# ECE3992_APS.net
KiCad netlist of a schematic drawn in EAGLE
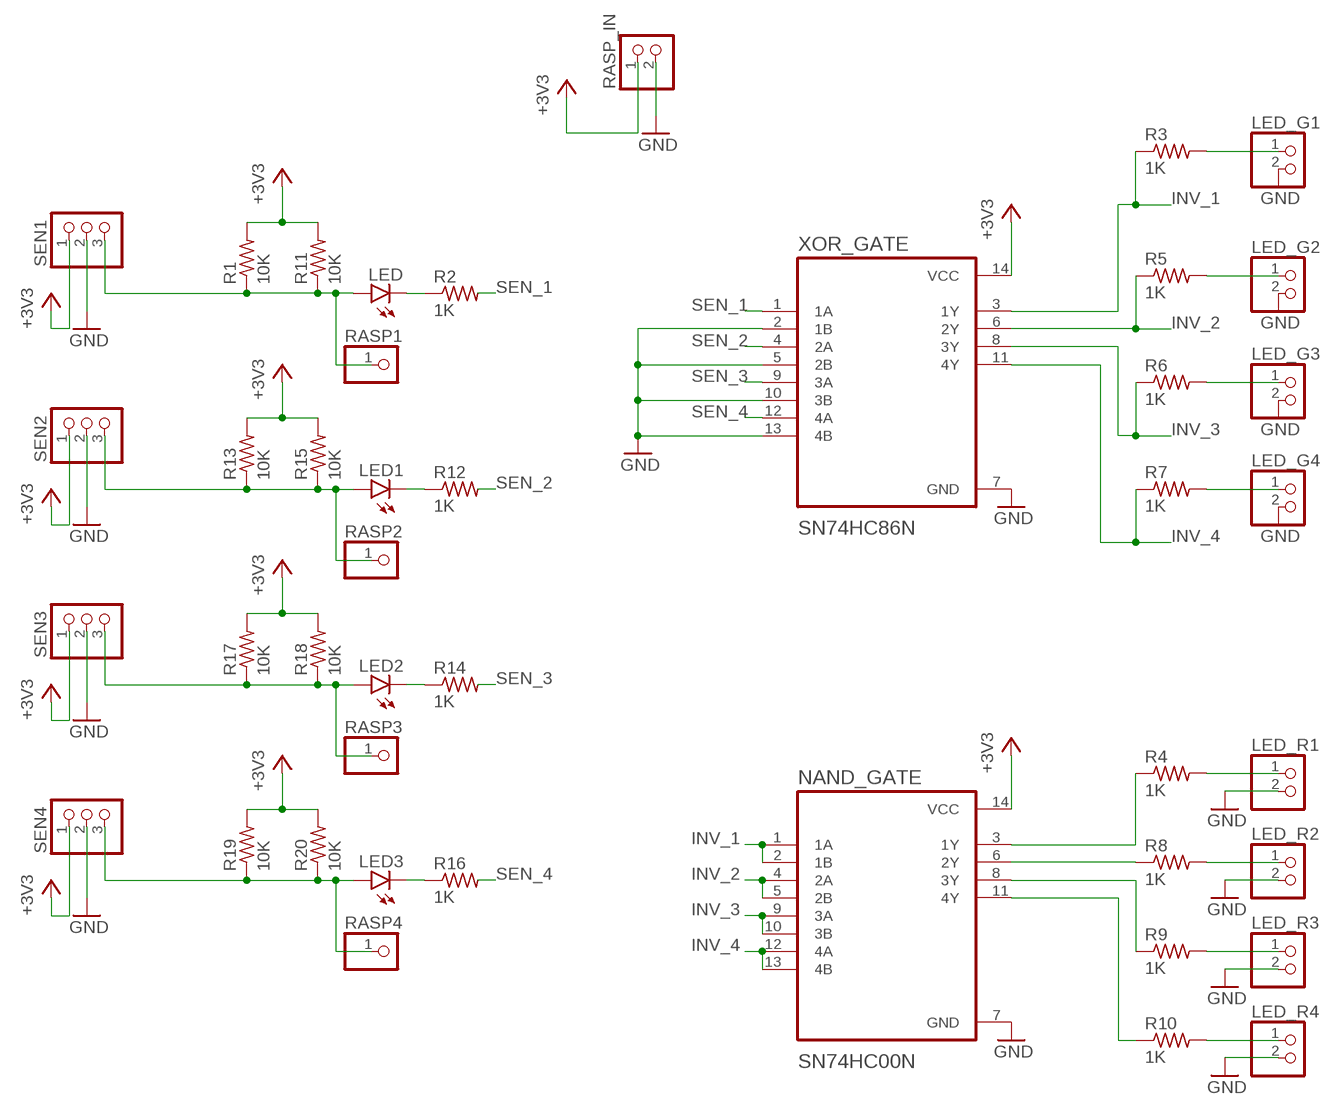
[diagram p0: schematic, sheet 1]

(export (version "E")
  (design (tool "Eeschema 10.0.6"))
  (components
    (comp (ref "LED")
      (value "LED5MM")
      (footprint "eagle-import:LED5MM")
      (libsource (lib "eagle-import") (part "LED5MM"))
    )
    (comp (ref "LED1")
      (value "LED5MM")
      (footprint "eagle-import:LED5MM")
      (libsource (lib "eagle-import") (part "LED5MM"))
    )
    (comp (ref "LED2")
      (value "LED5MM")
      (footprint "eagle-import:LED5MM")
      (libsource (lib "eagle-import") (part "LED5MM"))
    )
    (comp (ref "LED3")
      (value "LED5MM")
      (footprint "eagle-import:LED5MM")
      (libsource (lib "eagle-import") (part "LED5MM"))
    )
    (comp (ref "LED_G1")
      (value "PINHD-1X2")
      (footprint "eagle-import:1X02")
      (libsource (lib "eagle-import") (part "PINHD-1X2"))
    )
    (comp (ref "LED_G2")
      (value "PINHD-1X2")
      (footprint "eagle-import:1X02")
      (libsource (lib "eagle-import") (part "PINHD-1X2"))
    )
    (comp (ref "LED_G3")
      (value "PINHD-1X2")
      (footprint "eagle-import:1X02")
      (libsource (lib "eagle-import") (part "PINHD-1X2"))
    )
    (comp (ref "LED_G4")
      (value "PINHD-1X2")
      (footprint "eagle-import:1X02")
      (libsource (lib "eagle-import") (part "PINHD-1X2"))
    )
    (comp (ref "LED_R1")
      (value "PINHD-1X2")
      (footprint "eagle-import:1X02")
      (libsource (lib "eagle-import") (part "PINHD-1X2"))
    )
    (comp (ref "LED_R2")
      (value "PINHD-1X2")
      (footprint "eagle-import:1X02")
      (libsource (lib "eagle-import") (part "PINHD-1X2"))
    )
    (comp (ref "LED_R3")
      (value "PINHD-1X2")
      (footprint "eagle-import:1X02")
      (libsource (lib "eagle-import") (part "PINHD-1X2"))
    )
    (comp (ref "LED_R4")
      (value "PINHD-1X2")
      (footprint "eagle-import:1X02")
      (libsource (lib "eagle-import") (part "PINHD-1X2"))
    )
    (comp (ref "NAND_GATE")
      (value "SN74HC00N")
      (footprint "eagle-import:DIP794W45P254L1969H508Q14")
      (fields (field (name "MF") "Texas Instruments"))
      (libsource (lib "eagle-import") (part "SN74HC00N"))
    )
    (comp (ref "R1")
      (value "10K")
      (footprint "eagle-import:0207_10")
      (libsource (lib "eagle-import") (part "R-US_0207/10"))
    )
    (comp (ref "R2")
      (value "1K")
      (footprint "eagle-import:0207_10")
      (libsource (lib "eagle-import") (part "R-US_0207/10"))
    )
    (comp (ref "R3")
      (value "1K")
      (footprint "eagle-import:0207_10")
      (libsource (lib "eagle-import") (part "R-US_0207/10"))
    )
    (comp (ref "R4")
      (value "1K")
      (footprint "eagle-import:0207_10")
      (libsource (lib "eagle-import") (part "R-US_0207/10"))
    )
    (comp (ref "R5")
      (value "1K")
      (footprint "eagle-import:0207_10")
      (libsource (lib "eagle-import") (part "R-US_0207/10"))
    )
    (comp (ref "R6")
      (value "1K")
      (footprint "eagle-import:0207_10")
      (libsource (lib "eagle-import") (part "R-US_0207/10"))
    )
    (comp (ref "R7")
      (value "1K")
      (footprint "eagle-import:0207_10")
      (libsource (lib "eagle-import") (part "R-US_0207/10"))
    )
    (comp (ref "R8")
      (value "1K")
      (footprint "eagle-import:0207_10")
      (libsource (lib "eagle-import") (part "R-US_0207/10"))
    )
    (comp (ref "R9")
      (value "1K")
      (footprint "eagle-import:0207_10")
      (libsource (lib "eagle-import") (part "R-US_0207/10"))
    )
    (comp (ref "R10")
      (value "1K")
      (footprint "eagle-import:0207_10")
      (libsource (lib "eagle-import") (part "R-US_0207/10"))
    )
    (comp (ref "R11")
      (value "10K")
      (footprint "eagle-import:0207_10")
      (libsource (lib "eagle-import") (part "R-US_0207/10"))
    )
    (comp (ref "R12")
      (value "1K")
      (footprint "eagle-import:0207_10")
      (libsource (lib "eagle-import") (part "R-US_0207/10"))
    )
    (comp (ref "R13")
      (value "10K")
      (footprint "eagle-import:0207_10")
      (libsource (lib "eagle-import") (part "R-US_0207/10"))
    )
    (comp (ref "R14")
      (value "1K")
      (footprint "eagle-import:0207_10")
      (libsource (lib "eagle-import") (part "R-US_0207/10"))
    )
    (comp (ref "R15")
      (value "10K")
      (footprint "eagle-import:0207_10")
      (libsource (lib "eagle-import") (part "R-US_0207/10"))
    )
    (comp (ref "R16")
      (value "1K")
      (footprint "eagle-import:0207_10")
      (libsource (lib "eagle-import") (part "R-US_0207/10"))
    )
    (comp (ref "R17")
      (value "10K")
      (footprint "eagle-import:0207_10")
      (libsource (lib "eagle-import") (part "R-US_0207/10"))
    )
    (comp (ref "R18")
      (value "10K")
      (footprint "eagle-import:0207_10")
      (libsource (lib "eagle-import") (part "R-US_0207/10"))
    )
    (comp (ref "R19")
      (value "10K")
      (footprint "eagle-import:0207_10")
      (libsource (lib "eagle-import") (part "R-US_0207/10"))
    )
    (comp (ref "R20")
      (value "10K")
      (footprint "eagle-import:0207_10")
      (libsource (lib "eagle-import") (part "R-US_0207/10"))
    )
    (comp (ref "RASP1")
      (value "PINHD-1X1")
      (footprint "eagle-import:1X01")
      (libsource (lib "eagle-import") (part "PINHD-1X1"))
    )
    (comp (ref "RASP2")
      (value "PINHD-1X1")
      (footprint "eagle-import:1X01")
      (libsource (lib "eagle-import") (part "PINHD-1X1"))
    )
    (comp (ref "RASP3")
      (value "PINHD-1X1")
      (footprint "eagle-import:1X01")
      (libsource (lib "eagle-import") (part "PINHD-1X1"))
    )
    (comp (ref "RASP4")
      (value "PINHD-1X1")
      (footprint "eagle-import:1X01")
      (libsource (lib "eagle-import") (part "PINHD-1X1"))
    )
    (comp (ref "RASP_IN")
      (value "PINHD-1X2")
      (footprint "eagle-import:1X02")
      (libsource (lib "eagle-import") (part "PINHD-1X2"))
    )
    (comp (ref "SEN1")
      (value "PINHD-1X3")
      (footprint "eagle-import:1X03")
      (libsource (lib "eagle-import") (part "PINHD-1X3"))
    )
    (comp (ref "SEN2")
      (value "PINHD-1X3")
      (footprint "eagle-import:1X03")
      (libsource (lib "eagle-import") (part "PINHD-1X3"))
    )
    (comp (ref "SEN3")
      (value "PINHD-1X3")
      (footprint "eagle-import:1X03")
      (libsource (lib "eagle-import") (part "PINHD-1X3"))
    )
    (comp (ref "SEN4")
      (value "PINHD-1X3")
      (footprint "eagle-import:1X03")
      (libsource (lib "eagle-import") (part "PINHD-1X3"))
    )
    (comp (ref "XOR_GATE")
      (value "SN74HC86N")
      (footprint "eagle-import:DIP794W45P254L1969H508Q14")
      (fields (field (name "MF") "Texas Instruments"))
      (libsource (lib "eagle-import") (part "SN74HC86N"))
    )
  )
  (nets
    (net (code "1") (name "+3V3") (class "Default")
      (node (ref "NAND_GATE") (pin "14") (pinfunction "VCC_14") (pintype "power_in"))
      (node (ref "R1") (pin "2") (pinfunction "2_2") (pintype "passive"))
      (node (ref "R11") (pin "2") (pinfunction "2_2") (pintype "passive"))
      (node (ref "R13") (pin "2") (pinfunction "2_2") (pintype "passive"))
      (node (ref "R15") (pin "2") (pinfunction "2_2") (pintype "passive"))
      (node (ref "R17") (pin "2") (pinfunction "2_2") (pintype "passive"))
      (node (ref "R18") (pin "2") (pinfunction "2_2") (pintype "passive"))
      (node (ref "R19") (pin "2") (pinfunction "2_2") (pintype "passive"))
      (node (ref "R20") (pin "2") (pinfunction "2_2") (pintype "passive"))
      (node (ref "RASP_IN") (pin "1") (pinfunction "1_1") (pintype "passive"))
      (node (ref "SEN1") (pin "1") (pinfunction "1_1") (pintype "passive"))
      (node (ref "SEN2") (pin "1") (pinfunction "1_1") (pintype "passive"))
      (node (ref "SEN3") (pin "1") (pinfunction "1_1") (pintype "passive"))
      (node (ref "SEN4") (pin "1") (pinfunction "1_1") (pintype "passive"))
      (node (ref "XOR_GATE") (pin "14") (pinfunction "VCC_14") (pintype "power_in"))
    )
    (net (code "2") (name "/INV_1") (class "Default")
      (node (ref "NAND_GATE") (pin "1") (pinfunction "1A_1") (pintype "input"))
      (node (ref "NAND_GATE") (pin "2") (pinfunction "1B_2") (pintype "input"))
      (node (ref "R3") (pin "1") (pinfunction "1_1") (pintype "passive"))
      (node (ref "XOR_GATE") (pin "3") (pinfunction "1Y_3") (pintype "output"))
    )
    (net (code "3") (name "/INV_2") (class "Default")
      (node (ref "NAND_GATE") (pin "4") (pinfunction "2A_4") (pintype "input"))
      (node (ref "NAND_GATE") (pin "5") (pinfunction "2B_5") (pintype "input"))
      (node (ref "R5") (pin "1") (pinfunction "1_1") (pintype "passive"))
      (node (ref "XOR_GATE") (pin "6") (pinfunction "2Y_6") (pintype "output"))
    )
    (net (code "4") (name "/INV_3") (class "Default")
      (node (ref "NAND_GATE") (pin "10") (pinfunction "3B_10") (pintype "input"))
      (node (ref "NAND_GATE") (pin "9") (pinfunction "3A_9") (pintype "input"))
      (node (ref "R6") (pin "1") (pinfunction "1_1") (pintype "passive"))
      (node (ref "XOR_GATE") (pin "8") (pinfunction "3Y_8") (pintype "output"))
    )
    (net (code "5") (name "/INV_4") (class "Default")
      (node (ref "NAND_GATE") (pin "12") (pinfunction "4A_12") (pintype "input"))
      (node (ref "NAND_GATE") (pin "13") (pinfunction "4B_13") (pintype "input"))
      (node (ref "R7") (pin "1") (pinfunction "1_1") (pintype "passive"))
      (node (ref "XOR_GATE") (pin "11") (pinfunction "4Y_11") (pintype "output"))
    )
    (net (code "6") (name "/SEN_1") (class "Default")
      (node (ref "R2") (pin "2") (pinfunction "2_2") (pintype "passive"))
      (node (ref "XOR_GATE") (pin "1") (pinfunction "1A_1") (pintype "input"))
    )
    (net (code "7") (name "/SEN_2") (class "Default")
      (node (ref "R12") (pin "2") (pinfunction "2_2") (pintype "passive"))
      (node (ref "XOR_GATE") (pin "4") (pinfunction "2A_4") (pintype "input"))
    )
    (net (code "8") (name "/SEN_3") (class "Default")
      (node (ref "R14") (pin "2") (pinfunction "2_2") (pintype "passive"))
      (node (ref "XOR_GATE") (pin "9") (pinfunction "3A_9") (pintype "input"))
    )
    (net (code "9") (name "/SEN_4") (class "Default")
      (node (ref "R16") (pin "2") (pinfunction "2_2") (pintype "passive"))
      (node (ref "XOR_GATE") (pin "12") (pinfunction "4A_12") (pintype "input"))
    )
    (net (code "10") (name "GND") (class "Default")
      (node (ref "LED_G1") (pin "2") (pinfunction "2_2") (pintype "passive"))
      (node (ref "LED_G2") (pin "2") (pinfunction "2_2") (pintype "passive"))
      (node (ref "LED_G3") (pin "2") (pinfunction "2_2") (pintype "passive"))
      (node (ref "LED_G4") (pin "2") (pinfunction "2_2") (pintype "passive"))
      (node (ref "LED_R1") (pin "2") (pinfunction "2_2") (pintype "passive"))
      (node (ref "LED_R2") (pin "2") (pinfunction "2_2") (pintype "passive"))
      (node (ref "LED_R3") (pin "2") (pinfunction "2_2") (pintype "passive"))
      (node (ref "LED_R4") (pin "2") (pinfunction "2_2") (pintype "passive"))
      (node (ref "NAND_GATE") (pin "7") (pinfunction "GND_7") (pintype "power_in"))
      (node (ref "RASP_IN") (pin "2") (pinfunction "2_2") (pintype "passive"))
      (node (ref "SEN1") (pin "2") (pinfunction "2_2") (pintype "passive"))
      (node (ref "SEN2") (pin "2") (pinfunction "2_2") (pintype "passive"))
      (node (ref "SEN3") (pin "2") (pinfunction "2_2") (pintype "passive"))
      (node (ref "SEN4") (pin "2") (pinfunction "2_2") (pintype "passive"))
      (node (ref "XOR_GATE") (pin "10") (pinfunction "3B_10") (pintype "input"))
      (node (ref "XOR_GATE") (pin "13") (pinfunction "4B_13") (pintype "input"))
      (node (ref "XOR_GATE") (pin "2") (pinfunction "1B_2") (pintype "input"))
      (node (ref "XOR_GATE") (pin "5") (pinfunction "2B_5") (pintype "input"))
      (node (ref "XOR_GATE") (pin "7") (pinfunction "GND_7") (pintype "power_in"))
    )
    (net (code "11") (name "Net-(LED-C)") (class "Default")
      (node (ref "LED") (pin "K") (pinfunction "C_K") (pintype "passive"))
      (node (ref "R2") (pin "1") (pinfunction "1_1") (pintype "passive"))
    )
    (net (code "12") (name "Net-(LED-PadA)") (class "Default")
      (node (ref "LED") (pin "A") (pinfunction "A_A") (pintype "passive"))
      (node (ref "R1") (pin "1") (pinfunction "1_1") (pintype "passive"))
      (node (ref "R11") (pin "1") (pinfunction "1_1") (pintype "passive"))
      (node (ref "RASP1") (pin "1") (pinfunction "1_1") (pintype "passive"))
      (node (ref "SEN1") (pin "3") (pinfunction "3_3") (pintype "passive"))
    )
    (net (code "13") (name "Net-(LED1-C)") (class "Default")
      (node (ref "LED1") (pin "K") (pinfunction "C_K") (pintype "passive"))
      (node (ref "R12") (pin "1") (pinfunction "1_1") (pintype "passive"))
    )
    (net (code "14") (name "Net-(LED1-PadA)") (class "Default")
      (node (ref "LED1") (pin "A") (pinfunction "A_A") (pintype "passive"))
      (node (ref "R13") (pin "1") (pinfunction "1_1") (pintype "passive"))
      (node (ref "R15") (pin "1") (pinfunction "1_1") (pintype "passive"))
      (node (ref "RASP2") (pin "1") (pinfunction "1_1") (pintype "passive"))
      (node (ref "SEN2") (pin "3") (pinfunction "3_3") (pintype "passive"))
    )
    (net (code "15") (name "Net-(LED2-C)") (class "Default")
      (node (ref "LED2") (pin "K") (pinfunction "C_K") (pintype "passive"))
      (node (ref "R14") (pin "1") (pinfunction "1_1") (pintype "passive"))
    )
    (net (code "16") (name "Net-(LED2-PadA)") (class "Default")
      (node (ref "LED2") (pin "A") (pinfunction "A_A") (pintype "passive"))
      (node (ref "R17") (pin "1") (pinfunction "1_1") (pintype "passive"))
      (node (ref "R18") (pin "1") (pinfunction "1_1") (pintype "passive"))
      (node (ref "RASP3") (pin "1") (pinfunction "1_1") (pintype "passive"))
      (node (ref "SEN3") (pin "3") (pinfunction "3_3") (pintype "passive"))
    )
    (net (code "17") (name "Net-(LED3-C)") (class "Default")
      (node (ref "LED3") (pin "K") (pinfunction "C_K") (pintype "passive"))
      (node (ref "R16") (pin "1") (pinfunction "1_1") (pintype "passive"))
    )
    (net (code "18") (name "Net-(LED3-PadA)") (class "Default")
      (node (ref "LED3") (pin "A") (pinfunction "A_A") (pintype "passive"))
      (node (ref "R19") (pin "1") (pinfunction "1_1") (pintype "passive"))
      (node (ref "R20") (pin "1") (pinfunction "1_1") (pintype "passive"))
      (node (ref "RASP4") (pin "1") (pinfunction "1_1") (pintype "passive"))
      (node (ref "SEN4") (pin "3") (pinfunction "3_3") (pintype "passive"))
    )
    (net (code "19") (name "Net-(LED_G1-Pad1)") (class "Default")
      (node (ref "LED_G1") (pin "1") (pinfunction "1_1") (pintype "passive"))
      (node (ref "R3") (pin "2") (pinfunction "2_2") (pintype "passive"))
    )
    (net (code "20") (name "Net-(LED_G2-Pad1)") (class "Default")
      (node (ref "LED_G2") (pin "1") (pinfunction "1_1") (pintype "passive"))
      (node (ref "R5") (pin "2") (pinfunction "2_2") (pintype "passive"))
    )
    (net (code "21") (name "Net-(LED_G3-Pad1)") (class "Default")
      (node (ref "LED_G3") (pin "1") (pinfunction "1_1") (pintype "passive"))
      (node (ref "R6") (pin "2") (pinfunction "2_2") (pintype "passive"))
    )
    (net (code "22") (name "Net-(LED_G4-Pad1)") (class "Default")
      (node (ref "LED_G4") (pin "1") (pinfunction "1_1") (pintype "passive"))
      (node (ref "R7") (pin "2") (pinfunction "2_2") (pintype "passive"))
    )
    (net (code "23") (name "Net-(LED_R1-Pad1)") (class "Default")
      (node (ref "LED_R1") (pin "1") (pinfunction "1_1") (pintype "passive"))
      (node (ref "R4") (pin "2") (pinfunction "2_2") (pintype "passive"))
    )
    (net (code "24") (name "Net-(LED_R2-Pad1)") (class "Default")
      (node (ref "LED_R2") (pin "1") (pinfunction "1_1") (pintype "passive"))
      (node (ref "R8") (pin "2") (pinfunction "2_2") (pintype "passive"))
    )
    (net (code "25") (name "Net-(LED_R3-Pad1)") (class "Default")
      (node (ref "LED_R3") (pin "1") (pinfunction "1_1") (pintype "passive"))
      (node (ref "R9") (pin "2") (pinfunction "2_2") (pintype "passive"))
    )
    (net (code "26") (name "Net-(LED_R4-Pad1)") (class "Default")
      (node (ref "LED_R4") (pin "1") (pinfunction "1_1") (pintype "passive"))
      (node (ref "R10") (pin "2") (pinfunction "2_2") (pintype "passive"))
    )
    (net (code "27") (name "Net-(NAND_GATE-1Y)") (class "Default")
      (node (ref "NAND_GATE") (pin "3") (pinfunction "1Y_3") (pintype "output"))
      (node (ref "R4") (pin "1") (pinfunction "1_1") (pintype "passive"))
    )
    (net (code "28") (name "Net-(NAND_GATE-2Y)") (class "Default")
      (node (ref "NAND_GATE") (pin "6") (pinfunction "2Y_6") (pintype "output"))
      (node (ref "R8") (pin "1") (pinfunction "1_1") (pintype "passive"))
    )
    (net (code "29") (name "Net-(NAND_GATE-3Y)") (class "Default")
      (node (ref "NAND_GATE") (pin "8") (pinfunction "3Y_8") (pintype "output"))
      (node (ref "R9") (pin "1") (pinfunction "1_1") (pintype "passive"))
    )
    (net (code "30") (name "Net-(NAND_GATE-4Y)") (class "Default")
      (node (ref "NAND_GATE") (pin "11") (pinfunction "4Y_11") (pintype "output"))
      (node (ref "R10") (pin "1") (pinfunction "1_1") (pintype "passive"))
    )
  )
)
